# Comm_Sheet.net
KiCad netlist of a schematic drawn in Altium Designer
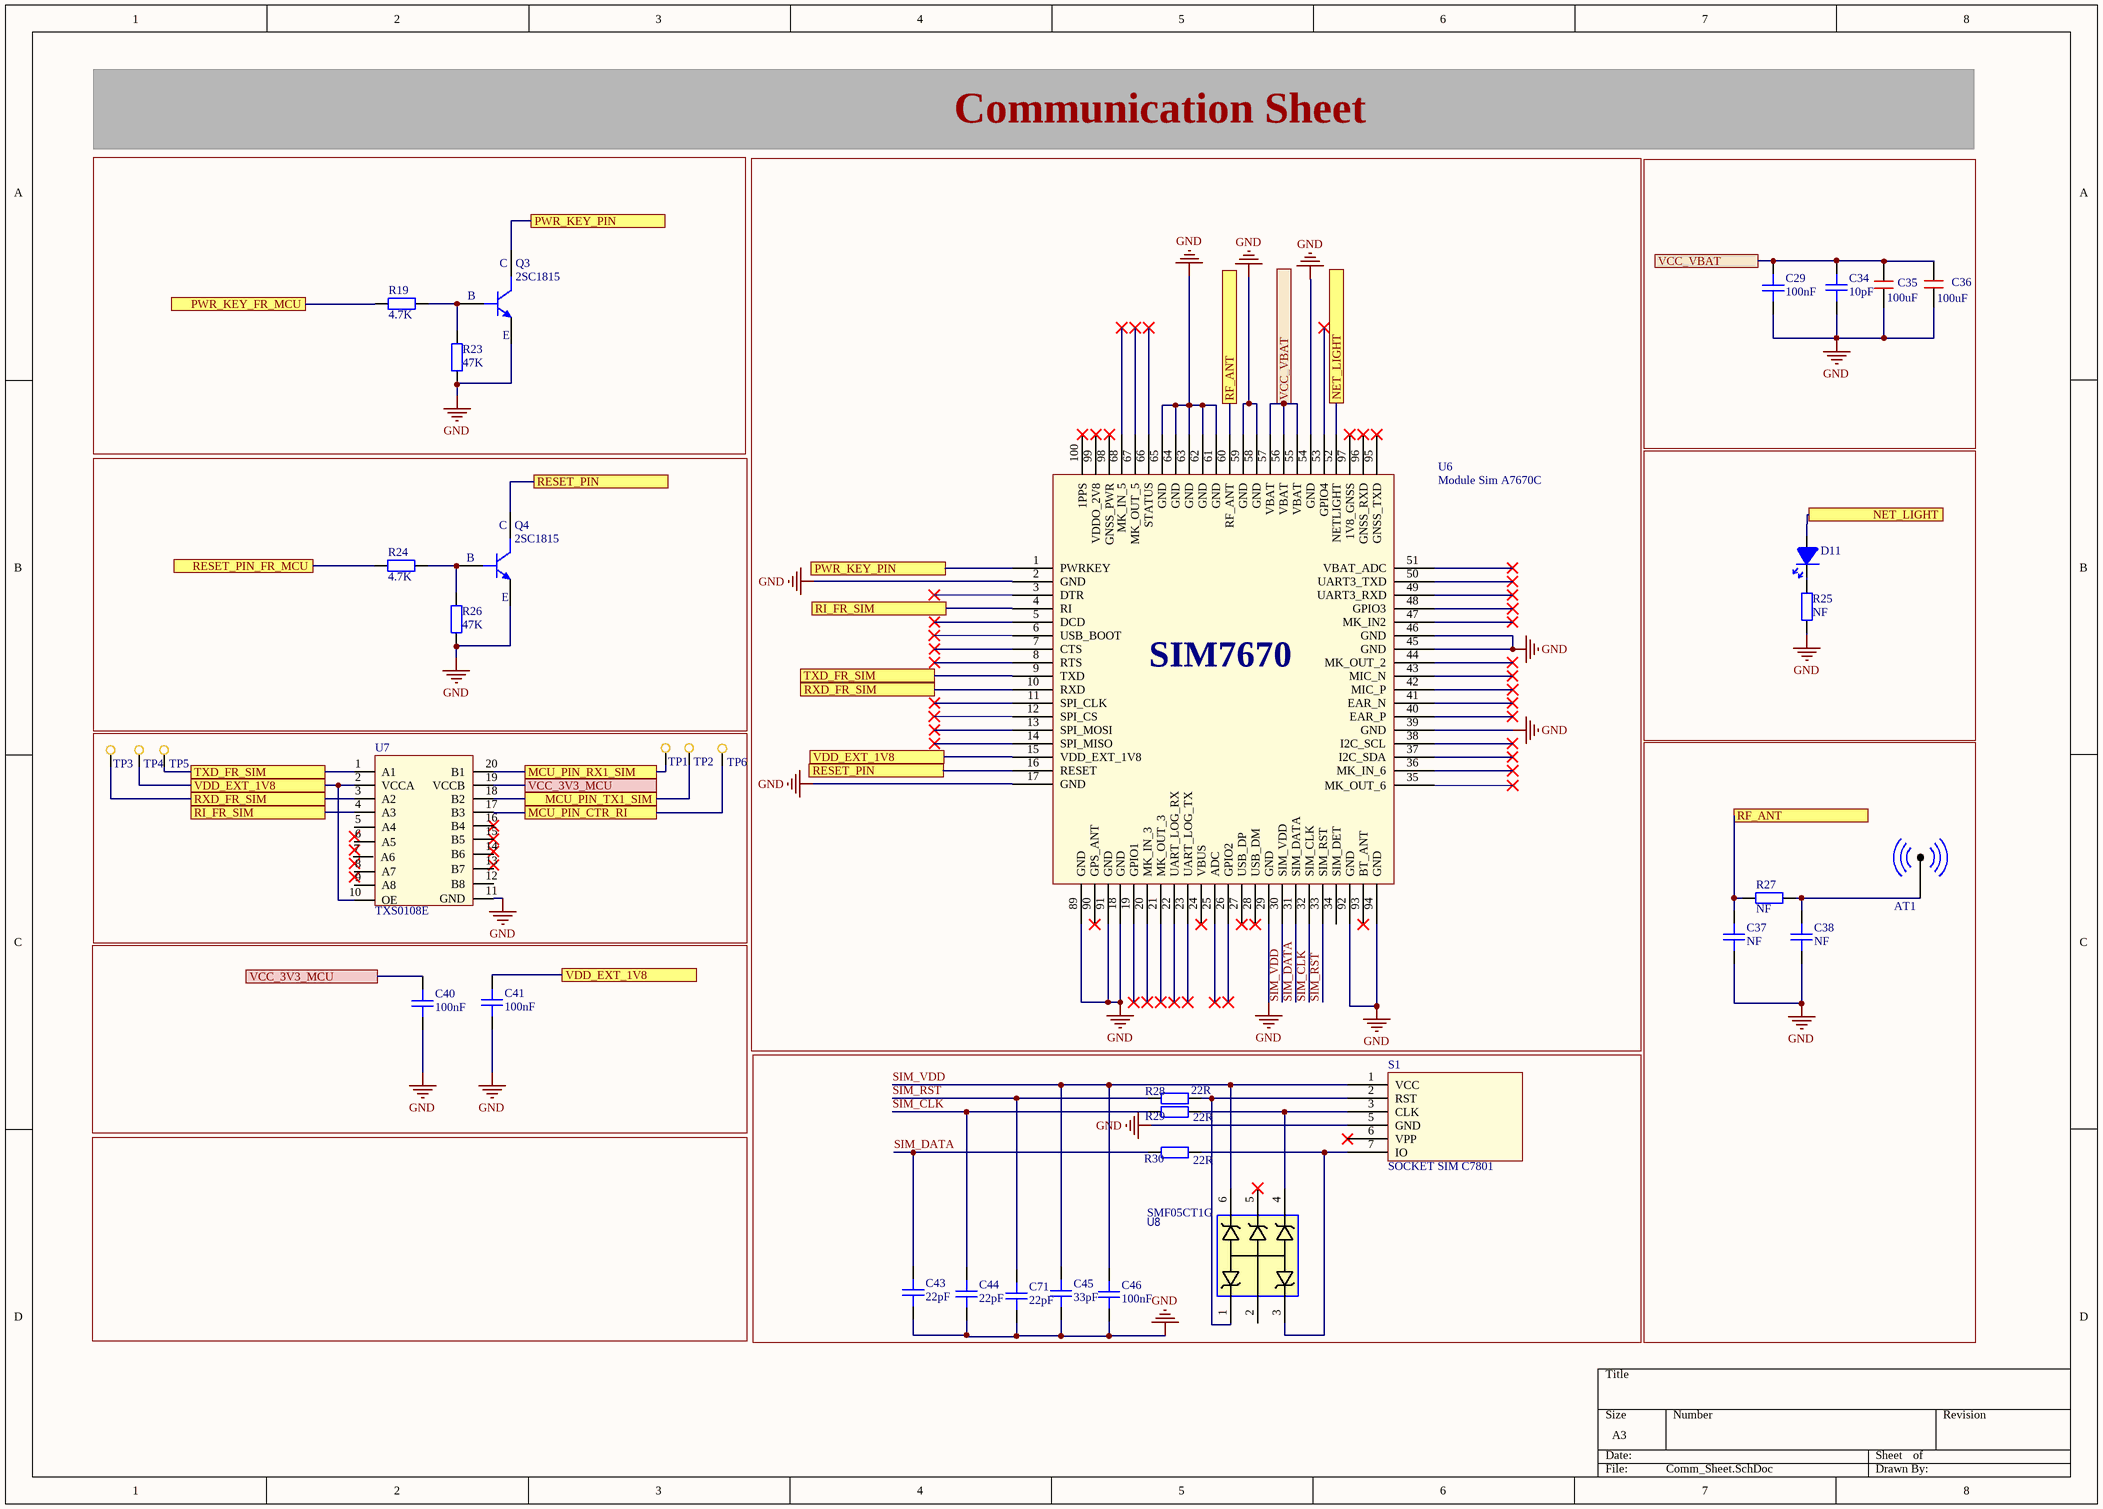
[diagram p0: Comm_Sheet.SchDoc]

(export (version "E")
  (design (tool "Eeschema 10.0.6"))
  (components
    (comp (ref "AT1")
      (value "AT-GSM-GPS")
      (footprint "ANTENA - SMA2")
      (description "CONNECTER ANTENNA GPS GSM")
      (fields (field (name "MPN") "RFCON171003SF6B001"))
      (libsource (lib "BYTECH_HW_LIB_2019") (part "RFCON171003SF6B001"))
    )
    (comp (ref "C29")
      (value "100nF")
      (footprint "CAPC-0603 (1608)")
      (description "CAP SMD, Not Fill, 0603")
      (libsource (lib "BYTECH_HW_LIB_2019") (part "CAPC NF 0603"))
    )
    (comp (ref "C34")
      (value "10pF")
      (footprint "CAPC-0603 (1608)")
      (description "CAP SMD, Not Fill, 0603")
      (libsource (lib "BYTECH_HW_LIB_2019") (part "CAPC NF 0603"))
    )
    (comp (ref "C35")
      (value "100uF")
      (footprint "100uF 1210 SMD")
      (libsource (lib "FM_Components") (part "CAP SMD 1210 100uF"))
    )
    (comp (ref "C36")
      (value "100uF")
      (footprint "100uF 1210 SMD")
      (libsource (lib "FM_Components") (part "CAP SMD 1210 100uF"))
    )
    (comp (ref "C37")
      (value "NF")
      (footprint "CAPC-0603 (1608)")
      (description "CAP SMD, Not Fill, 0603")
      (libsource (lib "BYTECH_HW_LIB_2019") (part "CAPC NF 0603"))
    )
    (comp (ref "C38")
      (value "NF")
      (footprint "CAPC-0603 (1608)")
      (description "CAP SMD, Not Fill, 0603")
      (libsource (lib "BYTECH_HW_LIB_2019") (part "CAPC NF 0603"))
    )
    (comp (ref "C40")
      (value "100nF")
      (footprint "CAPC-0603 (1608)")
      (description "CAP SMD, Not Fill, 0603")
      (libsource (lib "BYTECH_HW_LIB_2019") (part "CAPC NF 0603"))
    )
    (comp (ref "C41")
      (value "100nF")
      (footprint "CAPC-0603 (1608)")
      (description "CAP SMD, Not Fill, 0603")
      (libsource (lib "BYTECH_HW_LIB_2019") (part "CAPC NF 0603"))
    )
    (comp (ref "C43")
      (value "22pF")
      (footprint "CAPC-0603 (1608)")
      (description "CAP SMD, Not Fill, 0603")
      (libsource (lib "BYTECH_HW_LIB_2019") (part "CAPC NF 0603"))
    )
    (comp (ref "C44")
      (value "22pF")
      (footprint "CAPC-0603 (1608)")
      (description "CAP SMD, Not Fill, 0603")
      (libsource (lib "BYTECH_HW_LIB_2019") (part "CAPC NF 0603"))
    )
    (comp (ref "C45")
      (value "33pF")
      (footprint "CAPC-0603 (1608)")
      (description "CAP SMD, Not Fill, 0603")
      (libsource (lib "BYTECH_HW_LIB_2019") (part "CAPC NF 0603"))
    )
    (comp (ref "C46")
      (value "100nF")
      (footprint "CAPC-0603 (1608)")
      (description "CAP SMD, Not Fill, 0603")
      (libsource (lib "BYTECH_HW_LIB_2019") (part "CAPC NF 0603"))
    )
    (comp (ref "C71")
      (value "22pF")
      (footprint "CAPC-0603 (1608)")
      (description "CAP SMD, Not Fill, 0603")
      (libsource (lib "BYTECH_HW_LIB_2019") (part "CAPC NF 0603"))
    )
    (comp (ref "D11")
      (value "LED_0805_PW")
      (footprint "LED_0805_PW")
      (libsource (lib "FM_Components") (part "LED_0805_PW"))
    )
    (comp (ref "Q3")
      (value "2SC1815")
      (footprint "SOT23_3")
      (description "TRANS NPN 50V 0.15A SOT23-3")
      (libsource (lib "BYTECH_HW_LIB_2019") (part "2SC1815"))
    )
    (comp (ref "Q4")
      (value "2SC1815")
      (footprint "SOT23_3")
      (description "TRANS NPN 50V 0.15A SOT23-3")
      (libsource (lib "BYTECH_HW_LIB_2019") (part "2SC1815"))
    )
    (comp (ref "R19")
      (value "4.7K")
      (footprint "RESC-0603 (1608)")
      (description "RES SMD, Not Fill, 0603")
      (libsource (lib "BYTECH_HW_LIB_2019") (part "RESC NF 0603"))
    )
    (comp (ref "R23")
      (value "47K")
      (footprint "RESC-0603 (1608)")
      (description "RES SMD, Not Fill, 0603")
      (libsource (lib "") (part "RESC NF 0603_1"))
    )
    (comp (ref "R24")
      (value "4.7K")
      (footprint "RESC-0603 (1608)")
      (description "RES SMD, Not Fill, 0603")
      (libsource (lib "BYTECH_HW_LIB_2019") (part "RESC NF 0603"))
    )
    (comp (ref "R25")
      (value "NF")
      (footprint "RESC-0603 (1608)")
      (description "RES SMD, Not Fill, 0603")
      (libsource (lib "") (part "RESC NF 0603_2"))
    )
    (comp (ref "R26")
      (value "47K")
      (footprint "RESC-0603 (1608)")
      (description "RES SMD, Not Fill, 0603")
      (libsource (lib "") (part "RESC NF 0603_1"))
    )
    (comp (ref "R27")
      (value "NF")
      (footprint "RESC-0603 (1608)")
      (description "RES SMD, Not Fill, 0603")
      (libsource (lib "BYTECH_HW_LIB_2019") (part "RESC NF 0603"))
    )
    (comp (ref "R28")
      (value "22R")
      (footprint "RESC-0603 (1608)")
      (description "RES SMD, Not Fill, 0603")
      (libsource (lib "BYTECH_HW_LIB_2019") (part "RESC NF 0603"))
    )
    (comp (ref "R29")
      (value "22R")
      (footprint "RESC-0603 (1608)")
      (description "RES SMD, Not Fill, 0603")
      (libsource (lib "BYTECH_HW_LIB_2019") (part "RESC NF 0603"))
    )
    (comp (ref "R30")
      (value "22R")
      (footprint "RESC-0603 (1608)")
      (description "RES SMD, Not Fill, 0603")
      (libsource (lib "BYTECH_HW_LIB_2019") (part "RESC NF 0603"))
    )
    (comp (ref "S1")
      (value "SOCKET SIM C7801")
      (footprint "SOCKET SIM")
      (libsource (lib "FM_Components") (part "SOCKET SIM C7801"))
    )
    (comp (ref "TP1")
      (value "Testpoint-1mm")
      (footprint "TestPoint")
      (libsource (lib "FM_Components") (part "Testpoint-1mm"))
    )
    (comp (ref "TP2")
      (value "Testpoint-1mm")
      (footprint "TestPoint")
      (libsource (lib "FM_Components") (part "Testpoint-1mm"))
    )
    (comp (ref "TP3")
      (value "Testpoint-1mm")
      (footprint "TestPoint")
      (libsource (lib "FM_Components") (part "Testpoint-1mm"))
    )
    (comp (ref "TP4")
      (value "Testpoint-1mm")
      (footprint "TestPoint")
      (libsource (lib "FM_Components") (part "Testpoint-1mm"))
    )
    (comp (ref "TP5")
      (value "Testpoint-1mm")
      (footprint "TestPoint")
      (libsource (lib "FM_Components") (part "Testpoint-1mm"))
    )
    (comp (ref "TP6")
      (value "Testpoint-1mm")
      (footprint "TestPoint")
      (libsource (lib "FM_Components") (part "Testpoint-1mm"))
    )
    (comp (ref "U6")
      (value "Module Sim A7670C")
      (footprint "Module Sim A7670C")
      (libsource (lib "FM_Components") (part "Module Sim A7670C"))
    )
    (comp (ref "U7")
      (value "TXS0108E")
      (footprint "TXS0108E")
      (libsource (lib "FM_Components") (part "TXS0108E"))
    )
    (comp (ref "U8")
      (value "SMF05CT1G")
      (footprint "SOT363")
      (description "TVS DIODE 5VWM 12.5VC SC88")
      (libsource (lib "BYTECH_HW_LIB_2019") (part "SMF05CT1G"))
    )
  )
  (nets
    (net (code "1") (name "/MCU_PIN_CTR_RI") (class "Default")
      (node (ref "TP6") (pin "1") (pinfunction "1_1") (pintype "passive"))
      (node (ref "U7") (pin "17") (pinfunction "B3_17") (pintype "passive"))
    )
    (net (code "2") (name "/MCU_PIN_RX1_SIM") (class "Default")
      (node (ref "TP1") (pin "1") (pinfunction "1_1") (pintype "passive"))
      (node (ref "U7") (pin "20") (pinfunction "B1_20") (pintype "passive"))
    )
    (net (code "3") (name "/MCU_PIN_TX1_SIM") (class "Default")
      (node (ref "TP2") (pin "1") (pinfunction "1_1") (pintype "passive"))
      (node (ref "U7") (pin "18") (pinfunction "B2_18") (pintype "passive"))
    )
    (net (code "4") (name "/NET_LIGHT") (class "Default")
      (node (ref "D11") (pin "1") (pinfunction "A_1") (pintype "passive"))
      (node (ref "U6") (pin "52") (pinfunction "NETLIGHT_52") (pintype "passive"))
    )
    (net (code "5") (name "/PWR_KEY_FR_MCU") (class "Default")
      (node (ref "R19") (pin "2") (pinfunction "2_2") (pintype "passive"))
    )
    (net (code "6") (name "/PWR_KEY_PIN") (class "Default")
      (node (ref "Q3") (pin "3") (pinfunction "C_3") (pintype "passive"))
      (node (ref "U6") (pin "1") (pinfunction "PWRKEY_1") (pintype "passive"))
    )
    (net (code "7") (name "/RESET_PIN") (class "Default")
      (node (ref "Q4") (pin "3") (pinfunction "C_3") (pintype "passive"))
      (node (ref "U6") (pin "16") (pinfunction "RESET_16") (pintype "passive"))
    )
    (net (code "8") (name "/RESET_PIN_FR_MCU") (class "Default")
      (node (ref "R24") (pin "2") (pinfunction "2_2") (pintype "passive"))
    )
    (net (code "9") (name "/RF_ANT") (class "Default")
      (node (ref "C37") (pin "2") (pinfunction "2_2") (pintype "passive"))
      (node (ref "R27") (pin "2") (pinfunction "2_2") (pintype "passive"))
      (node (ref "U6") (pin "60") (pinfunction "RF_ANT_60") (pintype "passive"))
    )
    (net (code "10") (name "/RI_FR_SIM") (class "Default")
      (node (ref "U6") (pin "4") (pinfunction "RI_4") (pintype "passive"))
      (node (ref "U7") (pin "4") (pinfunction "A3_4") (pintype "passive"))
    )
    (net (code "11") (name "/RXD_FR_SIM") (class "Default")
      (node (ref "TP3") (pin "1") (pinfunction "1_1") (pintype "passive"))
      (node (ref "U6") (pin "10") (pinfunction "RXD_10") (pintype "passive"))
      (node (ref "U7") (pin "3") (pinfunction "A2_3") (pintype "passive"))
    )
    (net (code "12") (name "/SIM_CLK") (class "Default")
      (node (ref "C44") (pin "2") (pinfunction "2_2") (pintype "passive"))
      (node (ref "R29") (pin "2") (pinfunction "2_2") (pintype "passive"))
      (node (ref "U6") (pin "32") (pinfunction "SIM_CLK_32") (pintype "passive"))
    )
    (net (code "13") (name "/SIM_DATA") (class "Default")
      (node (ref "C43") (pin "2") (pinfunction "2_2") (pintype "passive"))
      (node (ref "R30") (pin "2") (pinfunction "2_2") (pintype "passive"))
      (node (ref "U6") (pin "31") (pinfunction "SIM_DATA_31") (pintype "passive"))
    )
    (net (code "14") (name "/SIM_RST") (class "Default")
      (node (ref "C71") (pin "2") (pinfunction "2_2") (pintype "passive"))
      (node (ref "R28") (pin "2") (pinfunction "2_2") (pintype "passive"))
      (node (ref "U6") (pin "33") (pinfunction "SIM_RST_33") (pintype "passive"))
    )
    (net (code "15") (name "/SIM_VDD") (class "Default")
      (node (ref "C45") (pin "2") (pinfunction "2_2") (pintype "passive"))
      (node (ref "C46") (pin "2") (pinfunction "2_2") (pintype "passive"))
      (node (ref "S1") (pin "1") (pinfunction "VCC_1") (pintype "passive"))
      (node (ref "U6") (pin "30") (pinfunction "SIM_VDD_30") (pintype "passive"))
      (node (ref "U8") (pin "6") (pinfunction "CT5_6") (pintype "passive"))
    )
    (net (code "16") (name "/TXD_FR_SIM") (class "Default")
      (node (ref "TP5") (pin "1") (pinfunction "1_1") (pintype "passive"))
      (node (ref "U6") (pin "9") (pinfunction "TXD_9") (pintype "passive"))
      (node (ref "U7") (pin "1") (pinfunction "A1_1") (pintype "passive"))
    )
    (net (code "17") (name "/VCC_3V3_MCU") (class "Default")
      (node (ref "C40") (pin "2") (pinfunction "2_2") (pintype "passive"))
      (node (ref "U7") (pin "19") (pinfunction "VCCB_19") (pintype "passive"))
    )
    (net (code "18") (name "/VCC_VBAT") (class "Default")
      (node (ref "C29") (pin "2") (pinfunction "2_2") (pintype "passive"))
      (node (ref "C34") (pin "2") (pinfunction "2_2") (pintype "passive"))
      (node (ref "C35") (pin "2") (pinfunction "2_2") (pintype "passive"))
      (node (ref "C36") (pin "2") (pinfunction "2_2") (pintype "passive"))
      (node (ref "U6") (pin "55") (pinfunction "VBAT_55") (pintype "passive"))
      (node (ref "U6") (pin "56") (pinfunction "VBAT_56") (pintype "passive"))
      (node (ref "U6") (pin "57") (pinfunction "VBAT_57") (pintype "passive"))
    )
    (net (code "19") (name "/VDD_EXT_1V8") (class "Default")
      (node (ref "C41") (pin "2") (pinfunction "2_2") (pintype "passive"))
      (node (ref "TP4") (pin "1") (pinfunction "1_1") (pintype "passive"))
      (node (ref "U6") (pin "15") (pinfunction "VDD_EXT_1V8_15") (pintype "passive"))
      (node (ref "U7") (pin "10") (pinfunction "OE_10") (pintype "passive"))
      (node (ref "U7") (pin "2") (pinfunction "VCCA_2") (pintype "passive"))
    )
    (net (code "20") (name "GND") (class "Default")
      (node (ref "C29") (pin "1") (pinfunction "1_1") (pintype "passive"))
      (node (ref "C34") (pin "1") (pinfunction "1_1") (pintype "passive"))
      (node (ref "C35") (pin "1") (pinfunction "1_1") (pintype "passive"))
      (node (ref "C36") (pin "1") (pinfunction "1_1") (pintype "passive"))
      (node (ref "C37") (pin "1") (pinfunction "1_1") (pintype "passive"))
      (node (ref "C38") (pin "1") (pinfunction "1_1") (pintype "passive"))
      (node (ref "C40") (pin "1") (pinfunction "1_1") (pintype "passive"))
      (node (ref "C41") (pin "1") (pinfunction "1_1") (pintype "passive"))
      (node (ref "C43") (pin "1") (pinfunction "1_1") (pintype "passive"))
      (node (ref "C44") (pin "1") (pinfunction "1_1") (pintype "passive"))
      (node (ref "C45") (pin "1") (pinfunction "1_1") (pintype "passive"))
      (node (ref "C46") (pin "1") (pinfunction "1_1") (pintype "passive"))
      (node (ref "C71") (pin "1") (pinfunction "1_1") (pintype "passive"))
      (node (ref "Q3") (pin "2") (pinfunction "E_2") (pintype "passive"))
      (node (ref "Q4") (pin "2") (pinfunction "E_2") (pintype "passive"))
      (node (ref "R23") (pin "2") (pinfunction "2_2") (pintype "passive"))
      (node (ref "R25") (pin "1") (pinfunction "1_1") (pintype "passive"))
      (node (ref "R26") (pin "2") (pinfunction "2_2") (pintype "passive"))
      (node (ref "S1") (pin "5") (pinfunction "GND_5") (pintype "passive"))
      (node (ref "U6") (pin "17") (pinfunction "GND_17") (pintype "passive"))
      (node (ref "U6") (pin "18") (pinfunction "GND_18") (pintype "passive"))
      (node (ref "U6") (pin "2") (pinfunction "GND_2") (pintype "passive"))
      (node (ref "U6") (pin "29") (pinfunction "GND_29") (pintype "passive"))
      (node (ref "U6") (pin "39") (pinfunction "GND_39") (pintype "passive"))
      (node (ref "U6") (pin "45") (pinfunction "GND_45") (pintype "passive"))
      (node (ref "U6") (pin "46") (pinfunction "GND_46") (pintype "passive"))
      (node (ref "U6") (pin "54") (pinfunction "GND_54") (pintype "passive"))
      (node (ref "U6") (pin "58") (pinfunction "GND_58") (pintype "passive"))
      (node (ref "U6") (pin "59") (pinfunction "GND_59") (pintype "passive"))
      (node (ref "U6") (pin "61") (pinfunction "GND_61") (pintype "passive"))
      (node (ref "U6") (pin "62") (pinfunction "GND_62") (pintype "passive"))
      (node (ref "U6") (pin "63") (pinfunction "GND_63") (pintype "passive"))
      (node (ref "U6") (pin "64") (pinfunction "GND_64") (pintype "passive"))
      (node (ref "U6") (pin "65") (pinfunction "GND_65") (pintype "passive"))
      (node (ref "U6") (pin "89") (pinfunction "GND_89") (pintype "passive"))
      (node (ref "U6") (pin "91") (pinfunction "GND_91") (pintype "passive"))
      (node (ref "U6") (pin "92") (pinfunction "GND_92") (pintype "passive"))
      (node (ref "U6") (pin "94") (pinfunction "GND_94") (pintype "passive"))
      (node (ref "U7") (pin "11") (pinfunction "GND_11") (pintype "passive"))
    )
    (net (code "21") (name "Net-(AT1-AT)") (class "Default")
      (node (ref "AT1") (pin "1") (pinfunction "AT_1") (pintype "passive"))
      (node (ref "C38") (pin "2") (pinfunction "2_2") (pintype "passive"))
      (node (ref "R27") (pin "1") (pinfunction "1_1") (pintype "passive"))
    )
    (net (code "22") (name "Net-(D11-K)") (class "Default")
      (node (ref "D11") (pin "2") (pinfunction "K_2") (pintype "passive"))
      (node (ref "R25") (pin "2") (pinfunction "2_2") (pintype "passive"))
    )
    (net (code "23") (name "Net-(Q3-B)") (class "Default")
      (node (ref "Q3") (pin "1") (pinfunction "B_1") (pintype "passive"))
      (node (ref "R19") (pin "1") (pinfunction "1_1") (pintype "passive"))
      (node (ref "R23") (pin "1") (pinfunction "1_1") (pintype "passive"))
    )
    (net (code "24") (name "Net-(Q4-B)") (class "Default")
      (node (ref "Q4") (pin "1") (pinfunction "B_1") (pintype "passive"))
      (node (ref "R24") (pin "1") (pinfunction "1_1") (pintype "passive"))
      (node (ref "R26") (pin "1") (pinfunction "1_1") (pintype "passive"))
    )
    (net (code "25") (name "Net-(S1-CLK)") (class "Default")
      (node (ref "R29") (pin "1") (pinfunction "1_1") (pintype "passive"))
      (node (ref "S1") (pin "3") (pinfunction "CLK_3") (pintype "passive"))
      (node (ref "U8") (pin "4") (pinfunction "CT3_4") (pintype "passive"))
    )
    (net (code "26") (name "Net-(S1-IO)") (class "Default")
      (node (ref "R30") (pin "1") (pinfunction "1_1") (pintype "passive"))
      (node (ref "S1") (pin "7") (pinfunction "IO_7") (pintype "passive"))
      (node (ref "U8") (pin "3") (pinfunction "CT2_3") (pintype "passive"))
    )
    (net (code "27") (name "Net-(S1-RST)") (class "Default")
      (node (ref "R28") (pin "1") (pinfunction "1_1") (pintype "passive"))
      (node (ref "S1") (pin "2") (pinfunction "RST_2") (pintype "passive"))
      (node (ref "U8") (pin "1") (pinfunction "CT1_1") (pintype "passive"))
    )
    (net (code "28") (name "unconnected-(AT1-Pad2)") (class "Default")
      (node (ref "AT1") (pin "2") (pinfunction "2_2") (pintype "passive"))
    )
    (net (code "29") (name "unconnected-(S1-VPP-Pad6)") (class "Default")
      (node (ref "S1") (pin "6") (pinfunction "VPP_6") (pintype "passive+no_connect"))
    )
    (net (code "30") (name "unconnected-(U6-1PPS-Pad100)") (class "Default")
      (node (ref "U6") (pin "100") (pinfunction "1PPS_100") (pintype "passive+no_connect"))
    )
    (net (code "31") (name "unconnected-(U6-1V8_GNSS-Pad97)") (class "Default")
      (node (ref "U6") (pin "97") (pinfunction "1V8_GNSS_97") (pintype "passive+no_connect"))
    )
    (net (code "32") (name "unconnected-(U6-ADC-Pad25)") (class "Default")
      (node (ref "U6") (pin "25") (pinfunction "ADC_25") (pintype "passive+no_connect"))
    )
    (net (code "33") (name "unconnected-(U6-BT_ANT-Pad93)") (class "Default")
      (node (ref "U6") (pin "93") (pinfunction "BT_ANT_93") (pintype "passive+no_connect"))
    )
    (net (code "34") (name "unconnected-(U6-CTS-Pad7)") (class "Default")
      (node (ref "U6") (pin "7") (pinfunction "CTS_7") (pintype "passive+no_connect"))
    )
    (net (code "35") (name "unconnected-(U6-DCD-Pad5)") (class "Default")
      (node (ref "U6") (pin "5") (pinfunction "DCD_5") (pintype "passive+no_connect"))
    )
    (net (code "36") (name "unconnected-(U6-DTR-Pad3)") (class "Default")
      (node (ref "U6") (pin "3") (pinfunction "DTR_3") (pintype "passive+no_connect"))
    )
    (net (code "37") (name "unconnected-(U6-EAR_N-Pad41)") (class "Default")
      (node (ref "U6") (pin "41") (pinfunction "EAR_N_41") (pintype "passive+no_connect"))
    )
    (net (code "38") (name "unconnected-(U6-EAR_P-Pad40)") (class "Default")
      (node (ref "U6") (pin "40") (pinfunction "EAR_P_40") (pintype "passive+no_connect"))
    )
    (net (code "39") (name "unconnected-(U6-GNSS_PWR-Pad98)") (class "Default")
      (node (ref "U6") (pin "98") (pinfunction "GNSS_PWR_98") (pintype "passive+no_connect"))
    )
    (net (code "40") (name "unconnected-(U6-GNSS_RXD-Pad96)") (class "Default")
      (node (ref "U6") (pin "96") (pinfunction "GNSS_RXD_96") (pintype "passive+no_connect"))
    )
    (net (code "41") (name "unconnected-(U6-GNSS_TXD-Pad95)") (class "Default")
      (node (ref "U6") (pin "95") (pinfunction "GNSS_TXD_95") (pintype "passive+no_connect"))
    )
    (net (code "42") (name "unconnected-(U6-GPIO1-Pad19)") (class "Default")
      (node (ref "U6") (pin "19") (pinfunction "GPIO1_19") (pintype "passive+no_connect"))
    )
    (net (code "43") (name "unconnected-(U6-GPIO2-Pad26)") (class "Default")
      (node (ref "U6") (pin "26") (pinfunction "GPIO2_26") (pintype "passive+no_connect"))
    )
    (net (code "44") (name "unconnected-(U6-GPIO3-Pad48)") (class "Default")
      (node (ref "U6") (pin "48") (pinfunction "GPIO3_48") (pintype "passive+no_connect"))
    )
    (net (code "45") (name "unconnected-(U6-GPIO4-Pad53)") (class "Default")
      (node (ref "U6") (pin "53") (pinfunction "GPIO4_53") (pintype "passive+no_connect"))
    )
    (net (code "46") (name "unconnected-(U6-GPS_ANT-Pad90)") (class "Default")
      (node (ref "U6") (pin "90") (pinfunction "GPS_ANT_90") (pintype "passive+no_connect"))
    )
    (net (code "47") (name "unconnected-(U6-I2C_SCL-Pad38)") (class "Default")
      (node (ref "U6") (pin "38") (pinfunction "I2C_SCL_38") (pintype "passive+no_connect"))
    )
    (net (code "48") (name "unconnected-(U6-I2C_SDA-Pad37)") (class "Default")
      (node (ref "U6") (pin "37") (pinfunction "I2C_SDA_37") (pintype "passive+no_connect"))
    )
    (net (code "49") (name "unconnected-(U6-MIC_N-Pad43)") (class "Default")
      (node (ref "U6") (pin "43") (pinfunction "MIC_N_43") (pintype "passive+no_connect"))
    )
    (net (code "50") (name "unconnected-(U6-MIC_P-Pad42)") (class "Default")
      (node (ref "U6") (pin "42") (pinfunction "MIC_P_42") (pintype "passive+no_connect"))
    )
    (net (code "51") (name "unconnected-(U6-MK_IN2-Pad47)") (class "Default")
      (node (ref "U6") (pin "47") (pinfunction "MK_IN2_47") (pintype "passive+no_connect"))
    )
    (net (code "52") (name "unconnected-(U6-MK_IN_3-Pad20)") (class "Default")
      (node (ref "U6") (pin "20") (pinfunction "MK_IN_3_20") (pintype "passive+no_connect"))
    )
    (net (code "53") (name "unconnected-(U6-MK_IN_5-Pad68)") (class "Default")
      (node (ref "U6") (pin "68") (pinfunction "MK_IN_5_68") (pintype "passive+no_connect"))
    )
    (net (code "54") (name "unconnected-(U6-MK_IN_6-Pad36)") (class "Default")
      (node (ref "U6") (pin "36") (pinfunction "MK_IN_6_36") (pintype "passive+no_connect"))
    )
    (net (code "55") (name "unconnected-(U6-MK_OUT_2-Pad44)") (class "Default")
      (node (ref "U6") (pin "44") (pinfunction "MK_OUT_2_44") (pintype "passive+no_connect"))
    )
    (net (code "56") (name "unconnected-(U6-MK_OUT_3-Pad21)") (class "Default")
      (node (ref "U6") (pin "21") (pinfunction "MK_OUT_3_21") (pintype "passive+no_connect"))
    )
    (net (code "57") (name "unconnected-(U6-MK_OUT_5-Pad67)") (class "Default")
      (node (ref "U6") (pin "67") (pinfunction "MK_OUT_5_67") (pintype "passive+no_connect"))
    )
    (net (code "58") (name "unconnected-(U6-MK_OUT_6-Pad35)") (class "Default")
      (node (ref "U6") (pin "35") (pinfunction "MK_OUT_6_35") (pintype "passive+no_connect"))
    )
    (net (code "59") (name "unconnected-(U6-RTS-Pad8)") (class "Default")
      (node (ref "U6") (pin "8") (pinfunction "RTS_8") (pintype "passive+no_connect"))
    )
    (net (code "60") (name "unconnected-(U6-SIM_DET-Pad34)") (class "Default")
      (node (ref "U6") (pin "34") (pinfunction "SIM_DET_34") (pintype "passive"))
    )
    (net (code "61") (name "unconnected-(U6-SPI_CLK-Pad11)") (class "Default")
      (node (ref "U6") (pin "11") (pinfunction "SPI_CLK_11") (pintype "passive+no_connect"))
    )
    (net (code "62") (name "unconnected-(U6-SPI_CS-Pad12)") (class "Default")
      (node (ref "U6") (pin "12") (pinfunction "SPI_CS_12") (pintype "passive+no_connect"))
    )
    (net (code "63") (name "unconnected-(U6-SPI_MISO-Pad14)") (class "Default")
      (node (ref "U6") (pin "14") (pinfunction "SPI_MISO_14") (pintype "passive+no_connect"))
    )
    (net (code "64") (name "unconnected-(U6-SPI_MOSI-Pad13)") (class "Default")
      (node (ref "U6") (pin "13") (pinfunction "SPI_MOSI_13") (pintype "passive+no_connect"))
    )
    (net (code "65") (name "unconnected-(U6-STATUS-Pad66)") (class "Default")
      (node (ref "U6") (pin "66") (pinfunction "STATUS_66") (pintype "passive+no_connect"))
    )
    (net (code "66") (name "unconnected-(U6-UART3_RXD-Pad49)") (class "Default")
      (node (ref "U6") (pin "49") (pinfunction "UART3_RXD_49") (pintype "passive+no_connect"))
    )
    (net (code "67") (name "unconnected-(U6-UART3_TXD-Pad50)") (class "Default")
      (node (ref "U6") (pin "50") (pinfunction "UART3_TXD_50") (pintype "passive+no_connect"))
    )
    (net (code "68") (name "unconnected-(U6-UART_LOG_RX-Pad22)") (class "Default")
      (node (ref "U6") (pin "22") (pinfunction "UART_LOG_RX_22") (pintype "passive+no_connect"))
    )
    (net (code "69") (name "unconnected-(U6-UART_LOG_TX-Pad23)") (class "Default")
      (node (ref "U6") (pin "23") (pinfunction "UART_LOG_TX_23") (pintype "passive+no_connect"))
    )
    (net (code "70") (name "unconnected-(U6-USB_BOOT-Pad6)") (class "Default")
      (node (ref "U6") (pin "6") (pinfunction "USB_BOOT_6") (pintype "passive+no_connect"))
    )
    (net (code "71") (name "unconnected-(U6-USB_DM-Pad28)") (class "Default")
      (node (ref "U6") (pin "28") (pinfunction "USB_DM_28") (pintype "passive+no_connect"))
    )
    (net (code "72") (name "unconnected-(U6-USB_DP-Pad27)") (class "Default")
      (node (ref "U6") (pin "27") (pinfunction "USB_DP_27") (pintype "passive+no_connect"))
    )
    (net (code "73") (name "unconnected-(U6-VBAT_ADC-Pad51)") (class "Default")
      (node (ref "U6") (pin "51") (pinfunction "VBAT_ADC_51") (pintype "passive+no_connect"))
    )
    (net (code "74") (name "unconnected-(U6-VBUS-Pad24)") (class "Default")
      (node (ref "U6") (pin "24") (pinfunction "VBUS_24") (pintype "passive+no_connect"))
    )
    (net (code "75") (name "unconnected-(U6-VDDO_2V8-Pad99)") (class "Default")
      (node (ref "U6") (pin "99") (pinfunction "VDDO_2V8_99") (pintype "passive+no_connect"))
    )
    (net (code "76") (name "unconnected-(U7-A4-Pad5)") (class "Default")
      (node (ref "U7") (pin "5") (pinfunction "A4_5") (pintype "passive"))
    )
    (net (code "77") (name "unconnected-(U7-A5-Pad6)") (class "Default")
      (node (ref "U7") (pin "6") (pinfunction "A5_6") (pintype "passive"))
    )
    (net (code "78") (name "unconnected-(U7-A6-Pad7)") (class "Default")
      (node (ref "U7") (pin "7") (pinfunction "A6_7") (pintype "passive"))
    )
    (net (code "79") (name "unconnected-(U7-A7-Pad8)") (class "Default")
      (node (ref "U7") (pin "8") (pinfunction "A7_8") (pintype "passive"))
    )
    (net (code "80") (name "unconnected-(U7-A8-Pad9)") (class "Default")
      (node (ref "U7") (pin "9") (pinfunction "A8_9") (pintype "passive"))
    )
    (net (code "81") (name "unconnected-(U7-B4-Pad16)") (class "Default")
      (node (ref "U7") (pin "16") (pinfunction "B4_16") (pintype "passive+no_connect"))
    )
    (net (code "82") (name "unconnected-(U7-B5-Pad15)") (class "Default")
      (node (ref "U7") (pin "15") (pinfunction "B5_15") (pintype "passive+no_connect"))
    )
    (net (code "83") (name "unconnected-(U7-B6-Pad14)") (class "Default")
      (node (ref "U7") (pin "14") (pinfunction "B6_14") (pintype "passive"))
    )
    (net (code "84") (name "unconnected-(U7-B7-Pad13)") (class "Default")
      (node (ref "U7") (pin "13") (pinfunction "B7_13") (pintype "passive"))
    )
    (net (code "85") (name "unconnected-(U7-B8-Pad12)") (class "Default")
      (node (ref "U7") (pin "12") (pinfunction "B8_12") (pintype "passive"))
    )
    (net (code "86") (name "unconnected-(U8-AN-Pad2)") (class "Default")
      (node (ref "U8") (pin "2") (pinfunction "AN_2") (pintype "passive"))
    )
    (net (code "87") (name "unconnected-(U8-CT4-Pad5)") (class "Default")
      (node (ref "U8") (pin "5") (pinfunction "CT4_5") (pintype "passive+no_connect"))
    )
  )
)
